# ONOFF2.net
KiCad netlist of a schematic drawn in EAGLE
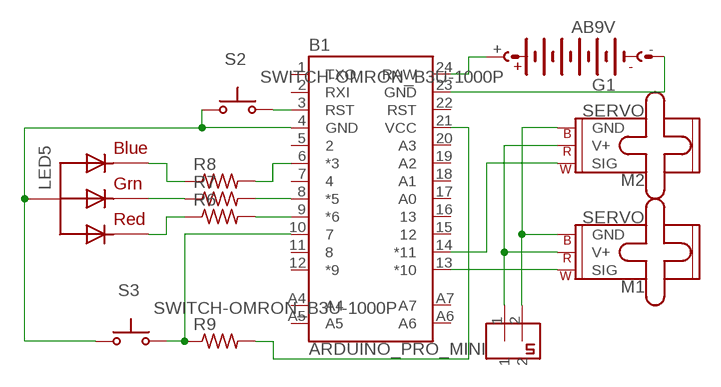
[diagram p0: schematic, sheet 1]

(export (version "E")
  (design (tool "Eeschema 10.0.6"))
  (components
    (comp (ref "B1")
      (value "ARDUINO_PRO_MINI")
      (footprint "eagle-import:ARDUINO_PRO_MINI")
      (libsource (lib "eagle-import") (part "ARDUINO_PRO_MINI"))
    )
    (comp (ref "CONNECTOR1")
      (value "2PIN")
      (footprint "eagle-import:2PIN")
      (libsource (lib "eagle-import") (part "2PIN"))
    )
    (comp (ref "G1")
      (value "AB9V")
      (footprint "eagle-import:AB9V")
      (libsource (lib "eagle-import") (part "AB9V"))
    )
    (comp (ref "LED5")
      (value "RGBLED_CA-5MM")
      (footprint "eagle-import:LED5MMRGB")
      (libsource (lib "eagle-import") (part "RGBLED_CA-5MM"))
    )
    (comp (ref "M1")
      (value "SERVO")
      (footprint "eagle-import:1X03")
      (libsource (lib "eagle-import") (part "SERVO"))
    )
    (comp (ref "M2")
      (value "SERVO")
      (footprint "eagle-import:1X03")
      (libsource (lib "eagle-import") (part "SERVO"))
    )
    (comp (ref "R6")
      (value "R-US_AXIAL-7.2MM-PITCH")
      (footprint "eagle-import:RESAD724W46L381D178B")
      (libsource (lib "eagle-import") (part "R-USAXIAL-7.2MM-PITCH_"))
    )
    (comp (ref "R7")
      (value "R-US_AXIAL-7.2MM-PITCH")
      (footprint "eagle-import:RESAD724W46L381D178B")
      (libsource (lib "eagle-import") (part "R-USAXIAL-7.2MM-PITCH_"))
    )
    (comp (ref "R8")
      (value "R-US_AXIAL-7.2MM-PITCH")
      (footprint "eagle-import:RESAD724W46L381D178B")
      (libsource (lib "eagle-import") (part "R-USAXIAL-7.2MM-PITCH_"))
    )
    (comp (ref "R9")
      (value "R-US_AXIAL-7.2MM-PITCH")
      (footprint "eagle-import:RESAD724W46L381D178B")
      (libsource (lib "eagle-import") (part "R-USAXIAL-7.2MM-PITCH_"))
    )
    (comp (ref "S2")
      (value "SWITCH-OMRON_B3U-1000P")
      (footprint "eagle-import:SWITCH-OMRON_B3U-1000P")
      (libsource (lib "eagle-import") (part "SWITCH-OMRON_B3U-1000P"))
    )
    (comp (ref "S3")
      (value "SWITCH-OMRON_B3U-1000P")
      (footprint "eagle-import:SWITCH-OMRON_B3U-1000P")
      (libsource (lib "eagle-import") (part "SWITCH-OMRON_B3U-1000P"))
    )
  )
  (nets
    (net (code "1") (name "Net-(B1-*3)") (class "Default")
      (node (ref "B1") (pin "6") (pinfunction "*3_6") (pintype "bidirectional"))
      (node (ref "R8") (pin "2") (pinfunction "2_2") (pintype "passive"))
    )
    (net (code "2") (name "Net-(B1-*5)") (class "Default")
      (node (ref "B1") (pin "8") (pinfunction "*5_8") (pintype "bidirectional"))
      (node (ref "R7") (pin "2") (pinfunction "2_2") (pintype "passive"))
    )
    (net (code "3") (name "Net-(B1-*6)") (class "Default")
      (node (ref "B1") (pin "9") (pinfunction "*6_9") (pintype "bidirectional"))
      (node (ref "R6") (pin "2") (pinfunction "2_2") (pintype "passive"))
    )
    (net (code "4") (name "Net-(B1-*10)") (class "Default")
      (node (ref "B1") (pin "13") (pinfunction "*10_13") (pintype "bidirectional"))
      (node (ref "M1") (pin "1") (pinfunction "SIG_1") (pintype "bidirectional"))
    )
    (net (code "5") (name "Net-(B1-*11)") (class "Default")
      (node (ref "B1") (pin "14") (pinfunction "*11_14") (pintype "bidirectional"))
      (node (ref "M2") (pin "1") (pinfunction "SIG_1") (pintype "bidirectional"))
    )
    (net (code "6") (name "Net-(B1-7)") (class "Default")
      (node (ref "B1") (pin "10") (pinfunction "7_10") (pintype "bidirectional"))
      (node (ref "R9") (pin "1") (pinfunction "1_1") (pintype "passive"))
      (node (ref "S3") (pin "2") (pinfunction "S_2") (pintype "passive"))
    )
    (net (code "7") (name "Net-(B1-GND-Pad23)") (class "Default")
      (node (ref "B1") (pin "23") (pinfunction "GND_23") (pintype "power_in"))
      (node (ref "G1") (pin "-") (pinfunction "-_-") (pintype "passive"))
    )
    (net (code "8") (name "Net-(B1-RAW)") (class "Default")
      (node (ref "B1") (pin "24") (pinfunction "RAW_24") (pintype "power_in"))
      (node (ref "G1") (pin "+") (pinfunction "+_+") (pintype "passive"))
    )
    (net (code "9") (name "Net-(B1-VCC)") (class "Default")
      (node (ref "B1") (pin "21") (pinfunction "VCC_21") (pintype "power_in"))
      (node (ref "R9") (pin "2") (pinfunction "2_2") (pintype "passive"))
    )
    (net (code "10") (name "Net-(LED5-BLUE)") (class "Default")
      (node (ref "LED5") (pin "4") (pinfunction "BLUE_4") (pintype "bidirectional"))
      (node (ref "R8") (pin "1") (pinfunction "1_1") (pintype "passive"))
    )
    (net (code "11") (name "Net-(LED5-GREEN)") (class "Default")
      (node (ref "LED5") (pin "3") (pinfunction "GREEN_3") (pintype "bidirectional"))
      (node (ref "R7") (pin "1") (pinfunction "1_1") (pintype "passive"))
    )
    (net (code "12") (name "Net-(LED5-RED)") (class "Default")
      (node (ref "LED5") (pin "1") (pinfunction "RED_1") (pintype "bidirectional"))
      (node (ref "R6") (pin "1") (pinfunction "1_1") (pintype "passive"))
    )
    (net (code "13") (name "Net-(LED5-VCC)") (class "Default")
      (node (ref "B1") (pin "4") (pinfunction "GND_4") (pintype "power_in"))
      (node (ref "LED5") (pin "2") (pinfunction "VCC_2") (pintype "bidirectional"))
      (node (ref "S2") (pin "1") (pinfunction "P_1") (pintype "passive"))
      (node (ref "S3") (pin "1") (pinfunction "P_1") (pintype "passive"))
    )
    (net (code "14") (name "Net-(M1-GND)") (class "Default")
      (node (ref "CONNECTOR1") (pin "2") (pinfunction "2_2") (pintype "bidirectional"))
      (node (ref "M1") (pin "3") (pinfunction "GND_3") (pintype "bidirectional"))
      (node (ref "M2") (pin "3") (pinfunction "GND_3") (pintype "bidirectional"))
    )
    (net (code "15") (name "Net-(M1-V+)") (class "Default")
      (node (ref "CONNECTOR1") (pin "1") (pinfunction "1_1") (pintype "bidirectional"))
      (node (ref "M1") (pin "2") (pinfunction "V+_2") (pintype "bidirectional"))
      (node (ref "M2") (pin "2") (pinfunction "V+_2") (pintype "bidirectional"))
    )
    (net (code "16") (name "Net-(S2-S)") (class "Default")
      (node (ref "B1") (pin "3") (pinfunction "RST_3") (pintype "bidirectional"))
      (node (ref "S2") (pin "2") (pinfunction "S_2") (pintype "passive"))
    )
    (net (code "17") (name "unconnected-(B1-*9-Pad12)") (class "Default")
      (node (ref "B1") (pin "12") (pinfunction "*9_12") (pintype "bidirectional"))
    )
    (net (code "18") (name "unconnected-(B1-2-Pad5)") (class "Default")
      (node (ref "B1") (pin "5") (pinfunction "2_5") (pintype "bidirectional"))
    )
    (net (code "19") (name "unconnected-(B1-4-Pad7)") (class "Default")
      (node (ref "B1") (pin "7") (pinfunction "4_7") (pintype "bidirectional"))
    )
    (net (code "20") (name "unconnected-(B1-8-Pad11)") (class "Default")
      (node (ref "B1") (pin "11") (pinfunction "8_11") (pintype "bidirectional"))
    )
    (net (code "21") (name "unconnected-(B1-12-Pad15)") (class "Default")
      (node (ref "B1") (pin "15") (pinfunction "12_15") (pintype "bidirectional"))
    )
    (net (code "22") (name "unconnected-(B1-13-Pad16)") (class "Default")
      (node (ref "B1") (pin "16") (pinfunction "13_16") (pintype "bidirectional"))
    )
    (net (code "23") (name "unconnected-(B1-A0-Pad17)") (class "Default")
      (node (ref "B1") (pin "17") (pinfunction "A0_17") (pintype "bidirectional"))
    )
    (net (code "24") (name "unconnected-(B1-A1-Pad18)") (class "Default")
      (node (ref "B1") (pin "18") (pinfunction "A1_18") (pintype "bidirectional"))
    )
    (net (code "25") (name "unconnected-(B1-A2-Pad19)") (class "Default")
      (node (ref "B1") (pin "19") (pinfunction "A2_19") (pintype "bidirectional"))
    )
    (net (code "26") (name "unconnected-(B1-A3-Pad20)") (class "Default")
      (node (ref "B1") (pin "20") (pinfunction "A3_20") (pintype "bidirectional"))
    )
    (net (code "27") (name "unconnected-(B1-PadA4)") (class "Default")
      (node (ref "B1") (pin "A4") (pinfunction "A4_A4") (pintype "bidirectional"))
    )
    (net (code "28") (name "unconnected-(B1-PadA5)") (class "Default")
      (node (ref "B1") (pin "A5") (pinfunction "A5_A5") (pintype "bidirectional"))
    )
    (net (code "29") (name "unconnected-(B1-PadA6)") (class "Default")
      (node (ref "B1") (pin "A6") (pinfunction "A6_A6") (pintype "bidirectional"))
    )
    (net (code "30") (name "unconnected-(B1-PadA7)") (class "Default")
      (node (ref "B1") (pin "A7") (pinfunction "A7_A7") (pintype "bidirectional"))
    )
    (net (code "31") (name "unconnected-(B1-RST-Pad22)") (class "Default")
      (node (ref "B1") (pin "22") (pinfunction "RST_22") (pintype "bidirectional"))
    )
    (net (code "32") (name "unconnected-(B1-RXI-Pad2)") (class "Default")
      (node (ref "B1") (pin "2") (pinfunction "RXI_2") (pintype "bidirectional"))
    )
    (net (code "33") (name "unconnected-(B1-TXO-Pad1)") (class "Default")
      (node (ref "B1") (pin "1") (pinfunction "TXO_1") (pintype "bidirectional"))
    )
  )
)
